# Host.net
KiCad netlist of a schematic drawn in Altium Designer
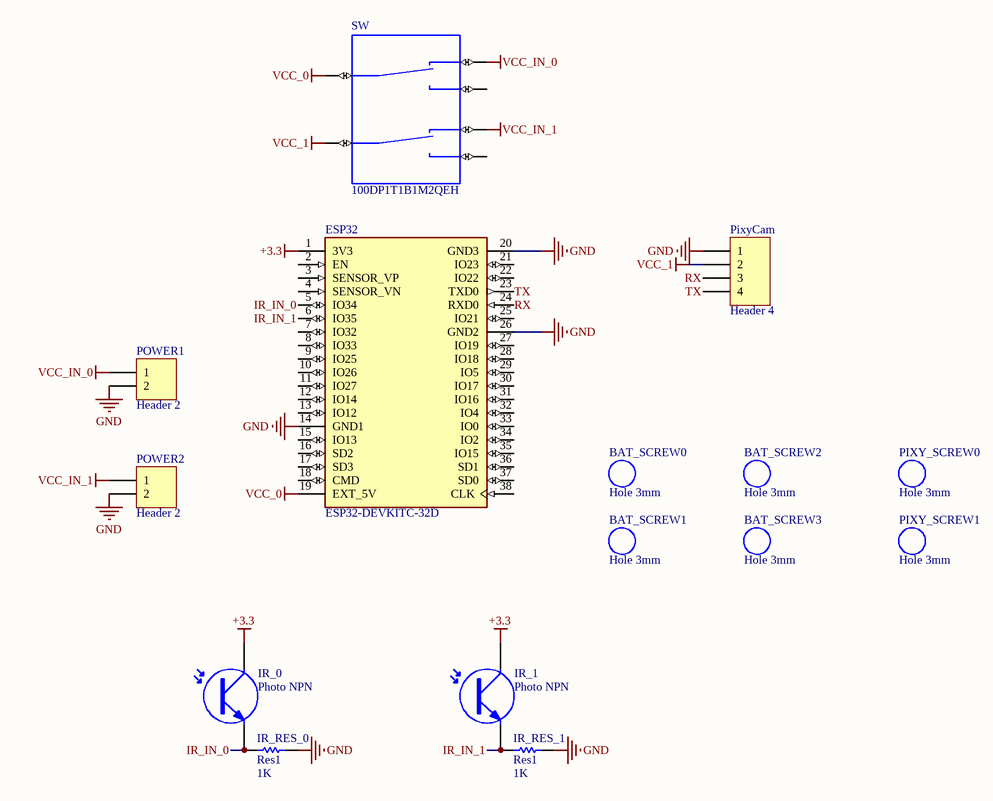
[diagram p0: Host.SchDoc]

(export (version "E")
  (design (tool "Eeschema 10.0.6"))
  (components
    (comp (ref "BAT_SCREW0")
      (value "Hole 3mm")
      (footprint "Hole 3mm")
      (libsource (lib "ECE LIB new") (part "Hole 3mm"))
    )
    (comp (ref "BAT_SCREW1")
      (value "Hole 3mm")
      (footprint "Hole 3mm")
      (libsource (lib "ECE LIB new") (part "Hole 3mm"))
    )
    (comp (ref "BAT_SCREW2")
      (value "Hole 3mm")
      (footprint "Hole 3mm")
      (libsource (lib "ECE LIB new") (part "Hole 3mm"))
    )
    (comp (ref "BAT_SCREW3")
      (value "Hole 3mm")
      (footprint "Hole 3mm")
      (libsource (lib "ECE LIB new") (part "Hole 3mm"))
    )
    (comp (ref "ESP32")
      (value "ESP32-DEVKITC-32D")
      (footprint "ESP32-NODEMCU")
      (fields (field (name "MF") "Espressif Systems"))
      (libsource (lib "ESP32-DEVKITC-32D") (part "ESP32-DEVKITC-32D"))
    )
    (comp (ref "IR_0")
      (value "Photo NPN")
      (footprint "IR_HEAD")
      (description "NPN Phototransistor")
      (fields (field (name "PUBLISHER") "Altium Limited"))
      (libsource (lib "Miscellaneous Devices") (part "Photo NPN"))
    )
    (comp (ref "IR_1")
      (value "Photo NPN")
      (footprint "IR_HEAD")
      (description "NPN Phototransistor")
      (fields (field (name "PUBLISHER") "Altium Limited"))
      (libsource (lib "Miscellaneous Devices") (part "Photo NPN"))
    )
    (comp (ref "IR_RES_0")
      (value "Res1")
      (footprint "AXIAL-0.3")
      (description "Resistor")
      (fields (field (name "ALTIUM_VALUE") "1K") (field (name "PUBLISHER") "Altium Limited"))
      (libsource (lib "Miscellaneous Devices") (part "Res1"))
    )
    (comp (ref "IR_RES_1")
      (value "Res1")
      (footprint "AXIAL-0.3")
      (description "Resistor")
      (fields (field (name "ALTIUM_VALUE") "1K") (field (name "PUBLISHER") "Altium Limited"))
      (libsource (lib "Miscellaneous Devices") (part "Res1"))
    )
    (comp (ref "PixyCam")
      (value "Header 4")
      (footprint "HDR1X4")
      (description "Header, 4-Pin")
      (fields (field (name "PUBLISHER") "Altium Limited"))
      (libsource (lib "Miscellaneous Connectors") (part "Header 4"))
    )
    (comp (ref "PIXY_SCREW0")
      (value "Hole 3mm")
      (footprint "Hole 3mm")
      (libsource (lib "ECE LIB new") (part "Hole 3mm"))
    )
    (comp (ref "PIXY_SCREW1")
      (value "Hole 3mm")
      (footprint "Hole 3mm")
      (libsource (lib "ECE LIB new") (part "Hole 3mm"))
    )
    (comp (ref "POWER1")
      (value "Header 2")
      (footprint "HDR1X2")
      (description "Header, 2-Pin")
      (fields (field (name "PUBLISHER") "Altium Limited"))
      (libsource (lib "Miscellaneous Connectors") (part "Header 2"))
    )
    (comp (ref "POWER2")
      (value "Header 2")
      (footprint "HDR1X2")
      (description "Header, 2-Pin")
      (fields (field (name "PUBLISHER") "Altium Limited"))
      (libsource (lib "Miscellaneous Connectors") (part "Header 2"))
    )
    (comp (ref "SW")
      (value "100DP1T1B1M2QEH")
      (footprint "100DP1T1B1M2QEH")
      (description "Toggle Switch DPDT Panel Mount")
      (fields (field (name "MF") "E-Switch"))
      (libsource (lib "100DP1T1B1M2QEH") (part "100DP1T1B1M2QEH"))
    )
  )
  (nets
    (net (code "1") (name "+3.3") (class "Default")
      (node (ref "ESP32") (pin "1") (pinfunction "3V3_1") (pintype "power_in"))
      (node (ref "IR_0") (pin "1") (pinfunction "C_1") (pintype "passive"))
      (node (ref "IR_1") (pin "1") (pinfunction "C_1") (pintype "passive"))
    )
    (net (code "2") (name "/IR_IN_0") (class "Default")
      (node (ref "ESP32") (pin "5") (pinfunction "IO34_5") (pintype "bidirectional"))
      (node (ref "IR_0") (pin "3") (pinfunction "E_3") (pintype "passive"))
      (node (ref "IR_RES_0") (pin "1") (pinfunction "1_1") (pintype "passive"))
    )
    (net (code "3") (name "/IR_IN_1") (class "Default")
      (node (ref "ESP32") (pin "6") (pinfunction "IO35_6") (pintype "bidirectional"))
      (node (ref "IR_1") (pin "3") (pinfunction "E_3") (pintype "passive"))
      (node (ref "IR_RES_1") (pin "1") (pinfunction "1_1") (pintype "passive"))
    )
    (net (code "4") (name "/RX") (class "Default")
      (node (ref "ESP32") (pin "24") (pinfunction "RXD0_24") (pintype "input"))
      (node (ref "PixyCam") (pin "3") (pinfunction "3_3") (pintype "passive"))
    )
    (net (code "5") (name "/TX") (class "Default")
      (node (ref "ESP32") (pin "23") (pinfunction "TXD0_23") (pintype "output"))
      (node (ref "PixyCam") (pin "4") (pinfunction "4_4") (pintype "passive"))
    )
    (net (code "6") (name "GND") (class "Default")
      (node (ref "ESP32") (pin "14") (pinfunction "GND1_14") (pintype "power_in"))
      (node (ref "ESP32") (pin "20") (pinfunction "GND3_20") (pintype "power_in"))
      (node (ref "ESP32") (pin "26") (pinfunction "GND2_26") (pintype "power_in"))
      (node (ref "IR_RES_0") (pin "2") (pinfunction "2_2") (pintype "passive"))
      (node (ref "IR_RES_1") (pin "2") (pinfunction "2_2") (pintype "passive"))
      (node (ref "POWER1") (pin "2") (pinfunction "2_2") (pintype "passive"))
      (node (ref "POWER2") (pin "2") (pinfunction "2_2") (pintype "passive"))
      (node (ref "PixyCam") (pin "1") (pinfunction "1_1") (pintype "passive"))
    )
    (net (code "7") (name "VCC_0") (class "Default")
      (node (ref "ESP32") (pin "19") (pinfunction "EXT_5V_19") (pintype "power_in"))
      (node (ref "SW") (pin "5") (pinfunction "5_5") (pintype "bidirectional"))
    )
    (net (code "8") (name "VCC_1") (class "Default")
      (node (ref "PixyCam") (pin "2") (pinfunction "2_2") (pintype "passive"))
      (node (ref "SW") (pin "2") (pinfunction "2_2") (pintype "bidirectional"))
    )
    (net (code "9") (name "VCC_IN_0") (class "Default")
      (node (ref "POWER1") (pin "1") (pinfunction "1_1") (pintype "passive"))
      (node (ref "SW") (pin "6") (pinfunction "6_6") (pintype "bidirectional"))
    )
    (net (code "10") (name "VCC_IN_1") (class "Default")
      (node (ref "POWER2") (pin "1") (pinfunction "1_1") (pintype "passive"))
      (node (ref "SW") (pin "3") (pinfunction "3_3") (pintype "bidirectional"))
    )
    (net (code "11") (name "unconnected-(ESP32-CLK-Pad38)") (class "Default")
      (node (ref "ESP32") (pin "38") (pinfunction "CLK_38") (pintype "input"))
    )
    (net (code "12") (name "unconnected-(ESP32-CMD-Pad18)") (class "Default")
      (node (ref "ESP32") (pin "18") (pinfunction "CMD_18") (pintype "bidirectional"))
    )
    (net (code "13") (name "unconnected-(ESP32-EN-Pad2)") (class "Default")
      (node (ref "ESP32") (pin "2") (pinfunction "EN_2") (pintype "input"))
    )
    (net (code "14") (name "unconnected-(ESP32-IO0-Pad33)") (class "Default")
      (node (ref "ESP32") (pin "33") (pinfunction "IO0_33") (pintype "bidirectional"))
    )
    (net (code "15") (name "unconnected-(ESP32-IO2-Pad34)") (class "Default")
      (node (ref "ESP32") (pin "34") (pinfunction "IO2_34") (pintype "bidirectional"))
    )
    (net (code "16") (name "unconnected-(ESP32-IO4-Pad32)") (class "Default")
      (node (ref "ESP32") (pin "32") (pinfunction "IO4_32") (pintype "bidirectional"))
    )
    (net (code "17") (name "unconnected-(ESP32-IO5-Pad29)") (class "Default")
      (node (ref "ESP32") (pin "29") (pinfunction "IO5_29") (pintype "bidirectional"))
    )
    (net (code "18") (name "unconnected-(ESP32-IO12-Pad13)") (class "Default")
      (node (ref "ESP32") (pin "13") (pinfunction "IO12_13") (pintype "bidirectional"))
    )
    (net (code "19") (name "unconnected-(ESP32-IO13-Pad15)") (class "Default")
      (node (ref "ESP32") (pin "15") (pinfunction "IO13_15") (pintype "bidirectional"))
    )
    (net (code "20") (name "unconnected-(ESP32-IO14-Pad12)") (class "Default")
      (node (ref "ESP32") (pin "12") (pinfunction "IO14_12") (pintype "bidirectional"))
    )
    (net (code "21") (name "unconnected-(ESP32-IO15-Pad35)") (class "Default")
      (node (ref "ESP32") (pin "35") (pinfunction "IO15_35") (pintype "bidirectional"))
    )
    (net (code "22") (name "unconnected-(ESP32-IO16-Pad31)") (class "Default")
      (node (ref "ESP32") (pin "31") (pinfunction "IO16_31") (pintype "bidirectional"))
    )
    (net (code "23") (name "unconnected-(ESP32-IO17-Pad30)") (class "Default")
      (node (ref "ESP32") (pin "30") (pinfunction "IO17_30") (pintype "bidirectional"))
    )
    (net (code "24") (name "unconnected-(ESP32-IO18-Pad28)") (class "Default")
      (node (ref "ESP32") (pin "28") (pinfunction "IO18_28") (pintype "bidirectional"))
    )
    (net (code "25") (name "unconnected-(ESP32-IO19-Pad27)") (class "Default")
      (node (ref "ESP32") (pin "27") (pinfunction "IO19_27") (pintype "bidirectional"))
    )
    (net (code "26") (name "unconnected-(ESP32-IO21-Pad25)") (class "Default")
      (node (ref "ESP32") (pin "25") (pinfunction "IO21_25") (pintype "bidirectional"))
    )
    (net (code "27") (name "unconnected-(ESP32-IO22-Pad22)") (class "Default")
      (node (ref "ESP32") (pin "22") (pinfunction "IO22_22") (pintype "bidirectional"))
    )
    (net (code "28") (name "unconnected-(ESP32-IO23-Pad21)") (class "Default")
      (node (ref "ESP32") (pin "21") (pinfunction "IO23_21") (pintype "bidirectional"))
    )
    (net (code "29") (name "unconnected-(ESP32-IO25-Pad9)") (class "Default")
      (node (ref "ESP32") (pin "9") (pinfunction "IO25_9") (pintype "bidirectional"))
    )
    (net (code "30") (name "unconnected-(ESP32-IO26-Pad10)") (class "Default")
      (node (ref "ESP32") (pin "10") (pinfunction "IO26_10") (pintype "bidirectional"))
    )
    (net (code "31") (name "unconnected-(ESP32-IO27-Pad11)") (class "Default")
      (node (ref "ESP32") (pin "11") (pinfunction "IO27_11") (pintype "bidirectional"))
    )
    (net (code "32") (name "unconnected-(ESP32-IO32-Pad7)") (class "Default")
      (node (ref "ESP32") (pin "7") (pinfunction "IO32_7") (pintype "bidirectional"))
    )
    (net (code "33") (name "unconnected-(ESP32-IO33-Pad8)") (class "Default")
      (node (ref "ESP32") (pin "8") (pinfunction "IO33_8") (pintype "bidirectional"))
    )
    (net (code "34") (name "unconnected-(ESP32-SD0-Pad37)") (class "Default")
      (node (ref "ESP32") (pin "37") (pinfunction "SD0_37") (pintype "bidirectional"))
    )
    (net (code "35") (name "unconnected-(ESP32-SD1-Pad36)") (class "Default")
      (node (ref "ESP32") (pin "36") (pinfunction "SD1_36") (pintype "bidirectional"))
    )
    (net (code "36") (name "unconnected-(ESP32-SD2-Pad16)") (class "Default")
      (node (ref "ESP32") (pin "16") (pinfunction "SD2_16") (pintype "bidirectional"))
    )
    (net (code "37") (name "unconnected-(ESP32-SD3-Pad17)") (class "Default")
      (node (ref "ESP32") (pin "17") (pinfunction "SD3_17") (pintype "bidirectional"))
    )
    (net (code "38") (name "unconnected-(ESP32-SENSOR_VN-Pad4)") (class "Default")
      (node (ref "ESP32") (pin "4") (pinfunction "SENSOR_VN_4") (pintype "input"))
    )
    (net (code "39") (name "unconnected-(ESP32-SENSOR_VP-Pad3)") (class "Default")
      (node (ref "ESP32") (pin "3") (pinfunction "SENSOR_VP_3") (pintype "input"))
    )
    (net (code "40") (name "unconnected-(SW-Pad1)") (class "Default")
      (node (ref "SW") (pin "1") (pinfunction "1_1") (pintype "bidirectional"))
    )
    (net (code "41") (name "unconnected-(SW-Pad4)") (class "Default")
      (node (ref "SW") (pin "4") (pinfunction "4_4") (pintype "bidirectional"))
    )
  )
)
